# IO_IIC.net
KiCad netlist of a schematic drawn in Altium Designer
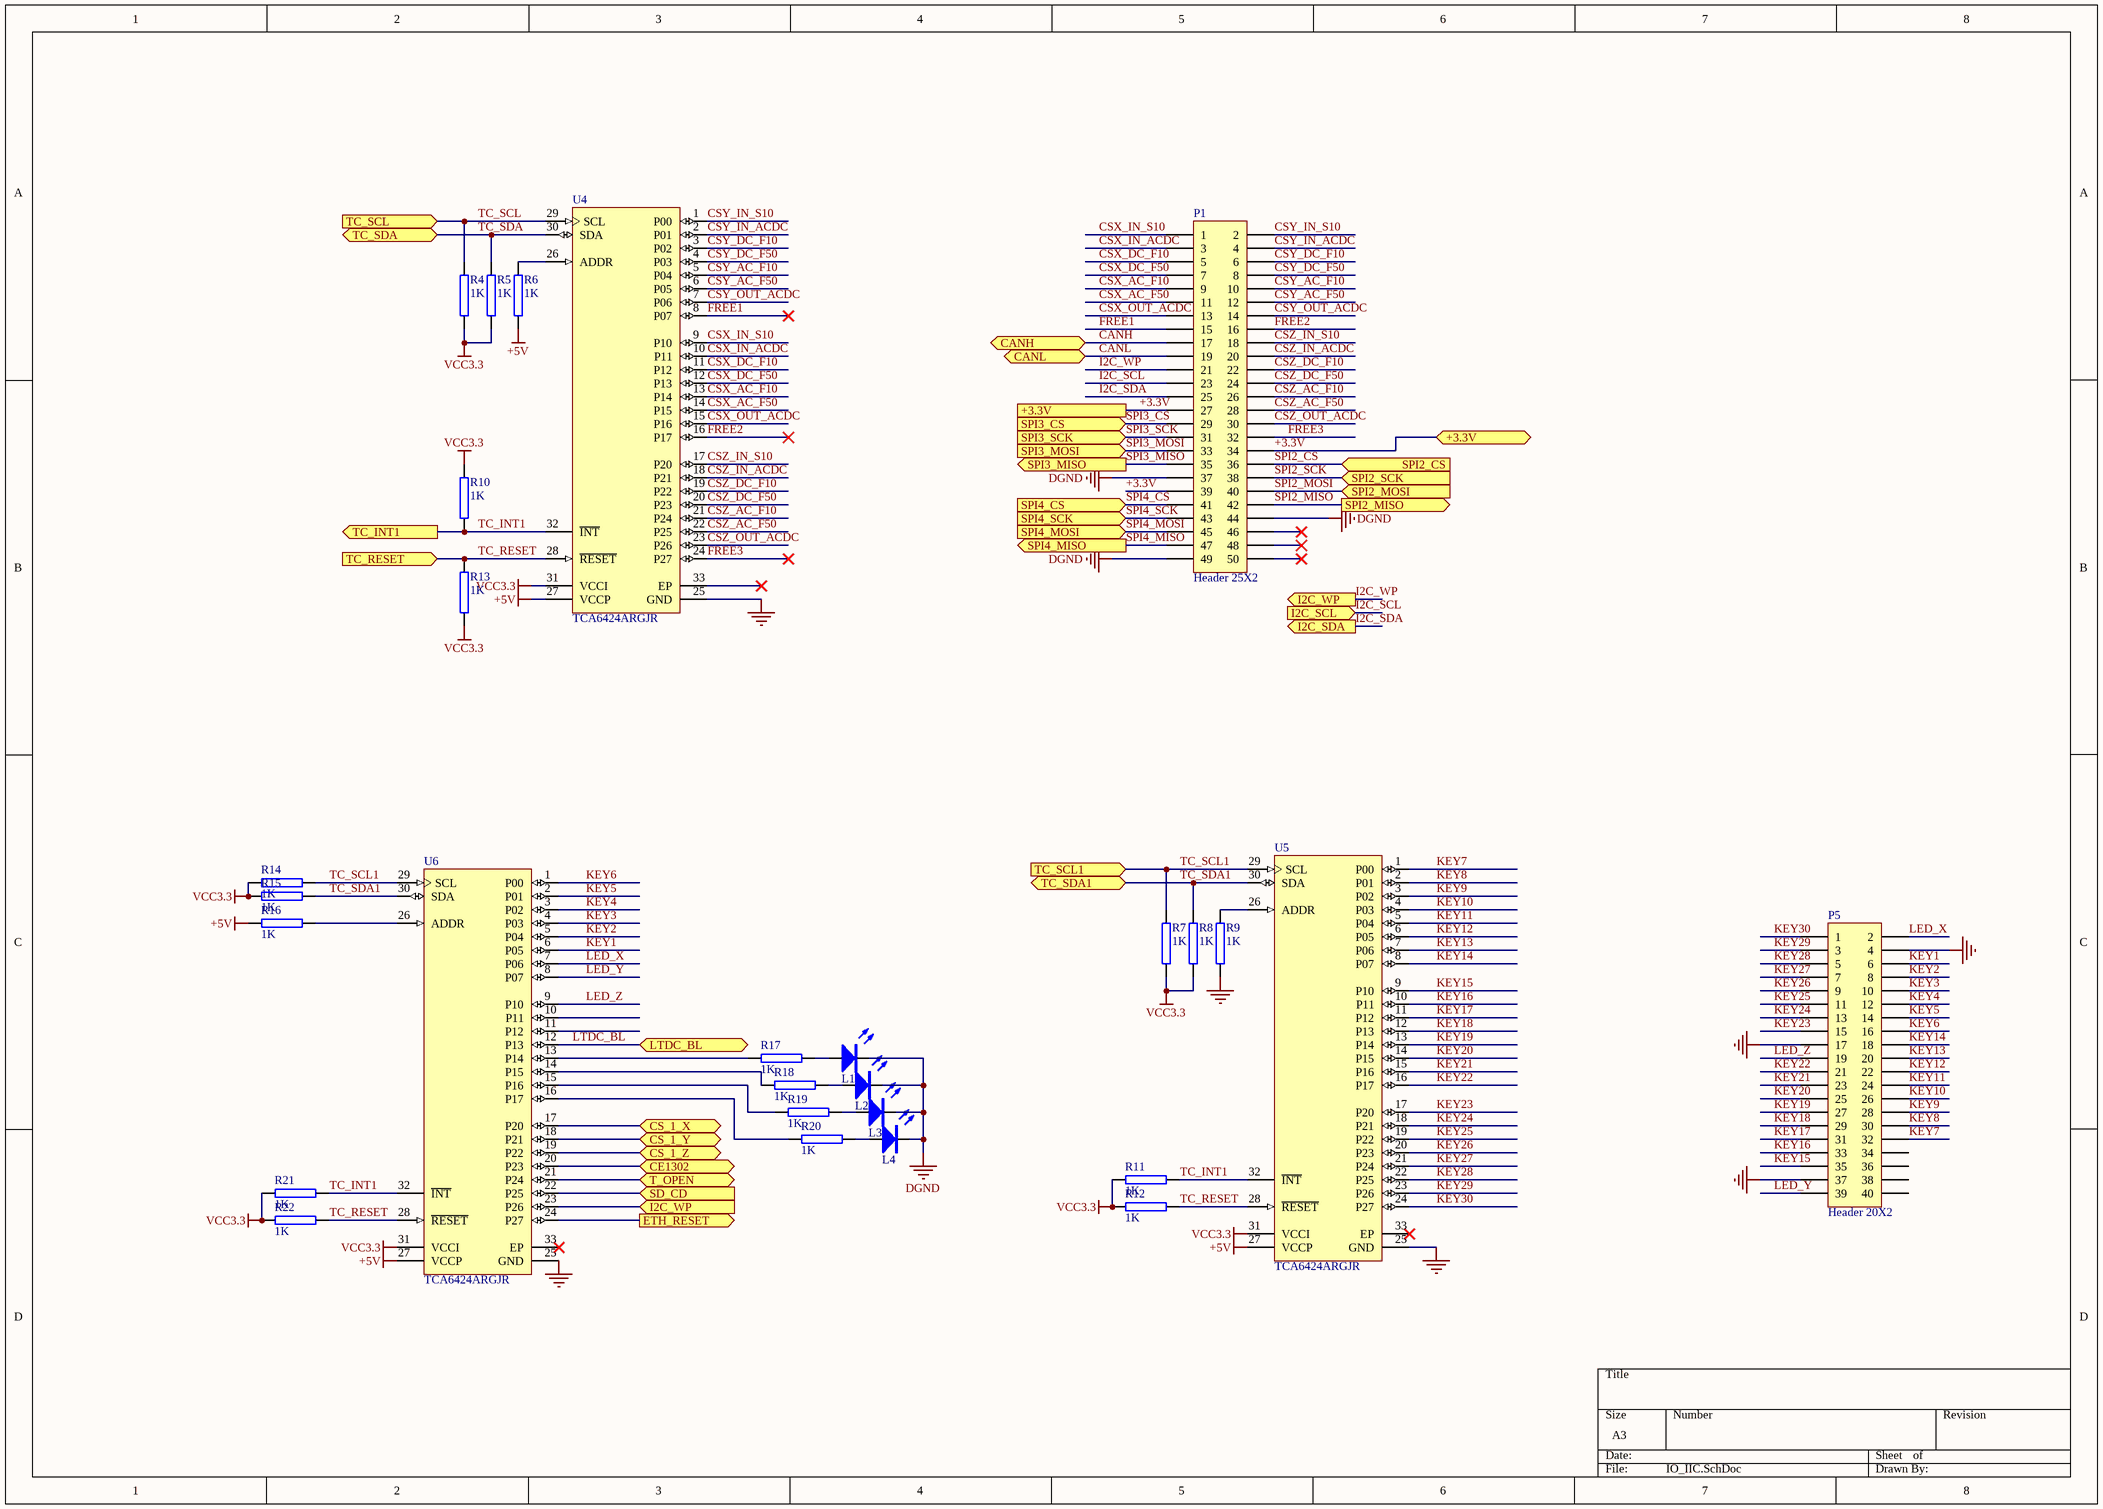
[diagram p0: IO_IIC.SchDoc]

(export (version "E")
  (design (tool "Eeschema 10.0.6"))
  (components
    (comp (ref "L1") (value "LED") (footprint "0805LED") (libsource (lib "二极管") (part "LED")))
    (comp (ref "L2") (value "LED") (footprint "0805LED") (libsource (lib "二极管") (part "LED")))
    (comp (ref "L3") (value "LED") (footprint "0805LED") (libsource (lib "二极管") (part "LED")))
    (comp (ref "L4") (value "LED") (footprint "0805LED") (libsource (lib "二极管") (part "LED")))
    (comp (ref "P1")
      (value "Header 25X2")
      (footprint "HDR2X25")
      (description "Header, 25-Pin, Dual row")
      (fields (field (name "PUBLISHER") "Altium Limited"))
      (libsource (lib "Miscellaneous Connectors") (part "Header 25X2"))
    )
    (comp (ref "P5")
      (value "Header 20X2")
      (footprint "HDR2X20")
      (description "Header, 20-Pin, Dual row")
      (fields (field (name "PUBLISHER") "Altium Limited"))
      (libsource (lib "Miscellaneous Connectors") (part "Header 20X2"))
    )
    (comp (ref "R4") (value "1K") (footprint "0603") (libsource (lib "电阻") (part "RES")))
    (comp (ref "R5") (value "1K") (footprint "0603") (libsource (lib "电阻") (part "RES")))
    (comp (ref "R6") (value "1K") (footprint "0603") (libsource (lib "电阻") (part "RES")))
    (comp (ref "R7") (value "1K") (footprint "0603") (libsource (lib "电阻") (part "RES")))
    (comp (ref "R8") (value "1K") (footprint "0603") (libsource (lib "电阻") (part "RES")))
    (comp (ref "R9") (value "1K") (footprint "0603") (libsource (lib "电阻") (part "RES")))
    (comp (ref "R10") (value "1K") (footprint "0603") (libsource (lib "电阻") (part "RES")))
    (comp (ref "R11") (value "1K") (footprint "0603") (libsource (lib "电阻") (part "RES")))
    (comp (ref "R12") (value "1K") (footprint "0603") (libsource (lib "电阻") (part "RES")))
    (comp (ref "R13") (value "1K") (footprint "0603") (libsource (lib "电阻") (part "RES")))
    (comp (ref "R14") (value "1K") (footprint "0603") (libsource (lib "电阻") (part "RES")))
    (comp (ref "R15") (value "1K") (footprint "0603") (libsource (lib "电阻") (part "RES")))
    (comp (ref "R16") (value "1K") (footprint "0603") (libsource (lib "电阻") (part "RES")))
    (comp (ref "R17") (value "1K") (footprint "0603") (libsource (lib "电阻") (part "RES")))
    (comp (ref "R18") (value "1K") (footprint "0603") (libsource (lib "电阻") (part "RES")))
    (comp (ref "R19") (value "1K") (footprint "0603") (libsource (lib "电阻") (part "RES")))
    (comp (ref "R20") (value "1K") (footprint "0603") (libsource (lib "电阻") (part "RES")))
    (comp (ref "R21") (value "1K") (footprint "0603") (libsource (lib "电阻") (part "RES")))
    (comp (ref "R22") (value "1K") (footprint "0603") (libsource (lib "电阻") (part "RES")))
    (comp (ref "U4")
      (value "TCA6424ARGJR")
      (footprint "TCA6424A-QFN32")
      (fields (field (name "MANUFACTURER") "Texas Instruments"))
      (libsource (lib "Texas Instruments Interface I2C") (part "TCA6424ARGJR"))
    )
    (comp (ref "U5")
      (value "TCA6424ARGJR")
      (footprint "TCA6424A-QFN32")
      (fields (field (name "MANUFACTURER") "Texas Instruments"))
      (libsource (lib "Texas Instruments Interface I2C") (part "TCA6424ARGJR"))
    )
    (comp (ref "U6")
      (value "TCA6424ARGJR")
      (footprint "TCA6424A-QFN32")
      (fields (field (name "MANUFACTURER") "Texas Instruments"))
      (libsource (lib "Texas Instruments Interface I2C") (part "TCA6424ARGJR"))
    )
  )
  (nets
    (net (code "1") (name "+5V") (class "Default")
      (node (ref "R16") (pin "2") (pinfunction "2_2") (pintype "passive"))
      (node (ref "R6") (pin "2") (pinfunction "2_2") (pintype "passive"))
      (node (ref "U4") (pin "27") (pinfunction "VCCP_27") (pintype "power_in"))
      (node (ref "U5") (pin "27") (pinfunction "VCCP_27") (pintype "power_in"))
      (node (ref "U6") (pin "27") (pinfunction "VCCP_27") (pintype "power_in"))
    )
    (net (code "2") (name "/+3.3V") (class "Default")
      (node (ref "P1") (pin "27") (pinfunction "27_27") (pintype "passive"))
      (node (ref "P1") (pin "34") (pinfunction "34_34") (pintype "passive"))
      (node (ref "P1") (pin "39") (pinfunction "39_39") (pintype "passive"))
    )
    (net (code "3") (name "/CANH") (class "Default")
      (node (ref "P1") (pin "17") (pinfunction "17_17") (pintype "passive"))
    )
    (net (code "4") (name "/CANL") (class "Default")
      (node (ref "P1") (pin "19") (pinfunction "19_19") (pintype "passive"))
    )
    (net (code "5") (name "/CE1302") (class "Default")
      (node (ref "U6") (pin "20") (pinfunction "P23_20") (pintype "bidirectional"))
    )
    (net (code "6") (name "/CSX_AC_F10") (class "Default")
      (node (ref "P1") (pin "9") (pinfunction "9_9") (pintype "passive"))
      (node (ref "U4") (pin "13") (pinfunction "P14_13") (pintype "bidirectional"))
    )
    (net (code "7") (name "/CSX_AC_F50") (class "Default")
      (node (ref "P1") (pin "11") (pinfunction "11_11") (pintype "passive"))
      (node (ref "U4") (pin "14") (pinfunction "P15_14") (pintype "bidirectional"))
    )
    (net (code "8") (name "/CSX_DC_F10") (class "Default")
      (node (ref "P1") (pin "5") (pinfunction "5_5") (pintype "passive"))
      (node (ref "U4") (pin "11") (pinfunction "P12_11") (pintype "bidirectional"))
    )
    (net (code "9") (name "/CSX_DC_F50") (class "Default")
      (node (ref "P1") (pin "7") (pinfunction "7_7") (pintype "passive"))
      (node (ref "U4") (pin "12") (pinfunction "P13_12") (pintype "bidirectional"))
    )
    (net (code "10") (name "/CSX_IN_ACDC") (class "Default")
      (node (ref "P1") (pin "3") (pinfunction "3_3") (pintype "passive"))
      (node (ref "U4") (pin "10") (pinfunction "P11_10") (pintype "bidirectional"))
    )
    (net (code "11") (name "/CSX_IN_S10") (class "Default")
      (node (ref "P1") (pin "1") (pinfunction "1_1") (pintype "passive"))
      (node (ref "U4") (pin "9") (pinfunction "P10_9") (pintype "bidirectional"))
    )
    (net (code "12") (name "/CSX_OUT_ACDC") (class "Default")
      (node (ref "P1") (pin "13") (pinfunction "13_13") (pintype "passive"))
      (node (ref "U4") (pin "15") (pinfunction "P16_15") (pintype "bidirectional"))
    )
    (net (code "13") (name "/CSY_AC_F10") (class "Default")
      (node (ref "P1") (pin "10") (pinfunction "10_10") (pintype "passive"))
      (node (ref "U4") (pin "5") (pinfunction "P04_5") (pintype "bidirectional"))
    )
    (net (code "14") (name "/CSY_AC_F50") (class "Default")
      (node (ref "P1") (pin "12") (pinfunction "12_12") (pintype "passive"))
      (node (ref "U4") (pin "6") (pinfunction "P05_6") (pintype "bidirectional"))
    )
    (net (code "15") (name "/CSY_DC_F10") (class "Default")
      (node (ref "P1") (pin "6") (pinfunction "6_6") (pintype "passive"))
      (node (ref "U4") (pin "3") (pinfunction "P02_3") (pintype "bidirectional"))
    )
    (net (code "16") (name "/CSY_DC_F50") (class "Default")
      (node (ref "P1") (pin "8") (pinfunction "8_8") (pintype "passive"))
      (node (ref "U4") (pin "4") (pinfunction "P03_4") (pintype "bidirectional"))
    )
    (net (code "17") (name "/CSY_IN_ACDC") (class "Default")
      (node (ref "P1") (pin "4") (pinfunction "4_4") (pintype "passive"))
      (node (ref "U4") (pin "2") (pinfunction "P01_2") (pintype "bidirectional"))
    )
    (net (code "18") (name "/CSY_IN_S10") (class "Default")
      (node (ref "P1") (pin "2") (pinfunction "2_2") (pintype "passive"))
      (node (ref "U4") (pin "1") (pinfunction "P00_1") (pintype "bidirectional"))
    )
    (net (code "19") (name "/CSY_OUT_ACDC") (class "Default")
      (node (ref "P1") (pin "14") (pinfunction "14_14") (pintype "passive"))
      (node (ref "U4") (pin "7") (pinfunction "P06_7") (pintype "bidirectional"))
    )
    (net (code "20") (name "/CSZ_AC_F10") (class "Default")
      (node (ref "P1") (pin "26") (pinfunction "26_26") (pintype "passive"))
      (node (ref "U4") (pin "21") (pinfunction "P24_21") (pintype "bidirectional"))
    )
    (net (code "21") (name "/CSZ_AC_F50") (class "Default")
      (node (ref "P1") (pin "28") (pinfunction "28_28") (pintype "passive"))
      (node (ref "U4") (pin "22") (pinfunction "P25_22") (pintype "bidirectional"))
    )
    (net (code "22") (name "/CSZ_DC_F10") (class "Default")
      (node (ref "P1") (pin "22") (pinfunction "22_22") (pintype "passive"))
      (node (ref "U4") (pin "19") (pinfunction "P22_19") (pintype "bidirectional"))
    )
    (net (code "23") (name "/CSZ_DC_F50") (class "Default")
      (node (ref "P1") (pin "24") (pinfunction "24_24") (pintype "passive"))
      (node (ref "U4") (pin "20") (pinfunction "P23_20") (pintype "bidirectional"))
    )
    (net (code "24") (name "/CSZ_IN_ACDC") (class "Default")
      (node (ref "P1") (pin "20") (pinfunction "20_20") (pintype "passive"))
      (node (ref "U4") (pin "18") (pinfunction "P21_18") (pintype "bidirectional"))
    )
    (net (code "25") (name "/CSZ_IN_S10") (class "Default")
      (node (ref "P1") (pin "18") (pinfunction "18_18") (pintype "passive"))
      (node (ref "U4") (pin "17") (pinfunction "P20_17") (pintype "bidirectional"))
    )
    (net (code "26") (name "/CSZ_OUT_ACDC") (class "Default")
      (node (ref "P1") (pin "30") (pinfunction "30_30") (pintype "passive"))
      (node (ref "U4") (pin "23") (pinfunction "P26_23") (pintype "bidirectional"))
    )
    (net (code "27") (name "/CS_1_X") (class "Default")
      (node (ref "U6") (pin "17") (pinfunction "P20_17") (pintype "bidirectional"))
    )
    (net (code "28") (name "/CS_1_Y") (class "Default")
      (node (ref "U6") (pin "18") (pinfunction "P21_18") (pintype "bidirectional"))
    )
    (net (code "29") (name "/CS_1_Z") (class "Default")
      (node (ref "U6") (pin "19") (pinfunction "P22_19") (pintype "bidirectional"))
    )
    (net (code "30") (name "/ETH_RESET") (class "Default")
      (node (ref "U6") (pin "24") (pinfunction "P27_24") (pintype "bidirectional"))
    )
    (net (code "31") (name "/FREE1") (class "Default")
      (node (ref "P1") (pin "15") (pinfunction "15_15") (pintype "passive"))
      (node (ref "U4") (pin "8") (pinfunction "P07_8") (pintype "bidirectional"))
    )
    (net (code "32") (name "/FREE2") (class "Default")
      (node (ref "P1") (pin "16") (pinfunction "16_16") (pintype "passive"))
      (node (ref "U4") (pin "16") (pinfunction "P17_16") (pintype "bidirectional"))
    )
    (net (code "33") (name "/FREE3") (class "Default")
      (node (ref "P1") (pin "32") (pinfunction "32_32") (pintype "passive"))
      (node (ref "U4") (pin "24") (pinfunction "P27_24") (pintype "bidirectional"))
    )
    (net (code "34") (name "/I2C_SCL") (class "Default")
      (node (ref "P1") (pin "23") (pinfunction "23_23") (pintype "passive"))
    )
    (net (code "35") (name "/I2C_SDA") (class "Default")
      (node (ref "P1") (pin "25") (pinfunction "25_25") (pintype "passive"))
    )
    (net (code "36") (name "/I2C_WP") (class "Default")
      (node (ref "P1") (pin "21") (pinfunction "21_21") (pintype "passive"))
      (node (ref "U6") (pin "23") (pinfunction "P26_23") (pintype "bidirectional"))
    )
    (net (code "37") (name "/KEY1") (class "Default")
      (node (ref "P5") (pin "6") (pinfunction "6_6") (pintype "passive"))
      (node (ref "U6") (pin "6") (pinfunction "P05_6") (pintype "bidirectional"))
    )
    (net (code "38") (name "/KEY2") (class "Default")
      (node (ref "P5") (pin "8") (pinfunction "8_8") (pintype "passive"))
      (node (ref "U6") (pin "5") (pinfunction "P04_5") (pintype "bidirectional"))
    )
    (net (code "39") (name "/KEY3") (class "Default")
      (node (ref "P5") (pin "10") (pinfunction "10_10") (pintype "passive"))
      (node (ref "U6") (pin "4") (pinfunction "P03_4") (pintype "bidirectional"))
    )
    (net (code "40") (name "/KEY4") (class "Default")
      (node (ref "P5") (pin "12") (pinfunction "12_12") (pintype "passive"))
      (node (ref "U6") (pin "3") (pinfunction "P02_3") (pintype "bidirectional"))
    )
    (net (code "41") (name "/KEY5") (class "Default")
      (node (ref "P5") (pin "14") (pinfunction "14_14") (pintype "passive"))
      (node (ref "U6") (pin "2") (pinfunction "P01_2") (pintype "bidirectional"))
    )
    (net (code "42") (name "/KEY6") (class "Default")
      (node (ref "P5") (pin "16") (pinfunction "16_16") (pintype "passive"))
      (node (ref "U6") (pin "1") (pinfunction "P00_1") (pintype "bidirectional"))
    )
    (net (code "43") (name "/KEY7") (class "Default")
      (node (ref "P5") (pin "32") (pinfunction "32_32") (pintype "passive"))
      (node (ref "U5") (pin "1") (pinfunction "P00_1") (pintype "bidirectional"))
    )
    (net (code "44") (name "/KEY8") (class "Default")
      (node (ref "P5") (pin "30") (pinfunction "30_30") (pintype "passive"))
      (node (ref "U5") (pin "2") (pinfunction "P01_2") (pintype "bidirectional"))
    )
    (net (code "45") (name "/KEY9") (class "Default")
      (node (ref "P5") (pin "28") (pinfunction "28_28") (pintype "passive"))
      (node (ref "U5") (pin "3") (pinfunction "P02_3") (pintype "bidirectional"))
    )
    (net (code "46") (name "/KEY10") (class "Default")
      (node (ref "P5") (pin "26") (pinfunction "26_26") (pintype "passive"))
      (node (ref "U5") (pin "4") (pinfunction "P03_4") (pintype "bidirectional"))
    )
    (net (code "47") (name "/KEY11") (class "Default")
      (node (ref "P5") (pin "24") (pinfunction "24_24") (pintype "passive"))
      (node (ref "U5") (pin "5") (pinfunction "P04_5") (pintype "bidirectional"))
    )
    (net (code "48") (name "/KEY12") (class "Default")
      (node (ref "P5") (pin "22") (pinfunction "22_22") (pintype "passive"))
      (node (ref "U5") (pin "6") (pinfunction "P05_6") (pintype "bidirectional"))
    )
    (net (code "49") (name "/KEY13") (class "Default")
      (node (ref "P5") (pin "20") (pinfunction "20_20") (pintype "passive"))
      (node (ref "U5") (pin "7") (pinfunction "P06_7") (pintype "bidirectional"))
    )
    (net (code "50") (name "/KEY14") (class "Default")
      (node (ref "P5") (pin "18") (pinfunction "18_18") (pintype "passive"))
      (node (ref "U5") (pin "8") (pinfunction "P07_8") (pintype "bidirectional"))
    )
    (net (code "51") (name "/KEY15") (class "Default")
      (node (ref "P5") (pin "35") (pinfunction "35_35") (pintype "passive"))
      (node (ref "U5") (pin "9") (pinfunction "P10_9") (pintype "bidirectional"))
    )
    (net (code "52") (name "/KEY16") (class "Default")
      (node (ref "P5") (pin "33") (pinfunction "33_33") (pintype "passive"))
      (node (ref "U5") (pin "10") (pinfunction "P11_10") (pintype "bidirectional"))
    )
    (net (code "53") (name "/KEY17") (class "Default")
      (node (ref "P5") (pin "31") (pinfunction "31_31") (pintype "passive"))
      (node (ref "U5") (pin "11") (pinfunction "P12_11") (pintype "bidirectional"))
    )
    (net (code "54") (name "/KEY18") (class "Default")
      (node (ref "P5") (pin "29") (pinfunction "29_29") (pintype "passive"))
      (node (ref "U5") (pin "12") (pinfunction "P13_12") (pintype "bidirectional"))
    )
    (net (code "55") (name "/KEY19") (class "Default")
      (node (ref "P5") (pin "27") (pinfunction "27_27") (pintype "passive"))
      (node (ref "U5") (pin "13") (pinfunction "P14_13") (pintype "bidirectional"))
    )
    (net (code "56") (name "/KEY20") (class "Default")
      (node (ref "P5") (pin "25") (pinfunction "25_25") (pintype "passive"))
      (node (ref "U5") (pin "14") (pinfunction "P15_14") (pintype "bidirectional"))
    )
    (net (code "57") (name "/KEY21") (class "Default")
      (node (ref "P5") (pin "23") (pinfunction "23_23") (pintype "passive"))
      (node (ref "U5") (pin "15") (pinfunction "P16_15") (pintype "bidirectional"))
    )
    (net (code "58") (name "/KEY22") (class "Default")
      (node (ref "P5") (pin "21") (pinfunction "21_21") (pintype "passive"))
      (node (ref "U5") (pin "16") (pinfunction "P17_16") (pintype "bidirectional"))
    )
    (net (code "59") (name "/KEY23") (class "Default")
      (node (ref "P5") (pin "15") (pinfunction "15_15") (pintype "passive"))
      (node (ref "U5") (pin "17") (pinfunction "P20_17") (pintype "bidirectional"))
    )
    (net (code "60") (name "/KEY24") (class "Default")
      (node (ref "P5") (pin "13") (pinfunction "13_13") (pintype "passive"))
      (node (ref "U5") (pin "18") (pinfunction "P21_18") (pintype "bidirectional"))
    )
    (net (code "61") (name "/KEY25") (class "Default")
      (node (ref "P5") (pin "11") (pinfunction "11_11") (pintype "passive"))
      (node (ref "U5") (pin "19") (pinfunction "P22_19") (pintype "bidirectional"))
    )
    (net (code "62") (name "/KEY26") (class "Default")
      (node (ref "P5") (pin "9") (pinfunction "9_9") (pintype "passive"))
      (node (ref "U5") (pin "20") (pinfunction "P23_20") (pintype "bidirectional"))
    )
    (net (code "63") (name "/KEY27") (class "Default")
      (node (ref "P5") (pin "7") (pinfunction "7_7") (pintype "passive"))
      (node (ref "U5") (pin "21") (pinfunction "P24_21") (pintype "bidirectional"))
    )
    (net (code "64") (name "/KEY28") (class "Default")
      (node (ref "P5") (pin "5") (pinfunction "5_5") (pintype "passive"))
      (node (ref "U5") (pin "22") (pinfunction "P25_22") (pintype "bidirectional"))
    )
    (net (code "65") (name "/KEY29") (class "Default")
      (node (ref "P5") (pin "3") (pinfunction "3_3") (pintype "passive"))
      (node (ref "U5") (pin "23") (pinfunction "P26_23") (pintype "bidirectional"))
    )
    (net (code "66") (name "/KEY30") (class "Default")
      (node (ref "P5") (pin "1") (pinfunction "1_1") (pintype "passive"))
      (node (ref "U5") (pin "24") (pinfunction "P27_24") (pintype "bidirectional"))
    )
    (net (code "67") (name "/LED_X") (class "Default")
      (node (ref "P5") (pin "2") (pinfunction "2_2") (pintype "passive"))
      (node (ref "U6") (pin "7") (pinfunction "P06_7") (pintype "bidirectional"))
    )
    (net (code "68") (name "/LED_Y") (class "Default")
      (node (ref "P5") (pin "39") (pinfunction "39_39") (pintype "passive"))
      (node (ref "U6") (pin "8") (pinfunction "P07_8") (pintype "bidirectional"))
    )
    (net (code "69") (name "/LED_Z") (class "Default")
      (node (ref "P5") (pin "19") (pinfunction "19_19") (pintype "passive"))
      (node (ref "U6") (pin "9") (pinfunction "P10_9") (pintype "bidirectional"))
    )
    (net (code "70") (name "/LTDC_BL") (class "Default")
      (node (ref "U6") (pin "12") (pinfunction "P13_12") (pintype "bidirectional"))
    )
    (net (code "71") (name "/SD_CD") (class "Default")
      (node (ref "U6") (pin "22") (pinfunction "P25_22") (pintype "bidirectional"))
    )
    (net (code "72") (name "/SPI2_CS") (class "Default")
      (node (ref "P1") (pin "36") (pinfunction "36_36") (pintype "passive"))
    )
    (net (code "73") (name "/SPI2_MISO") (class "Default")
      (node (ref "P1") (pin "42") (pinfunction "42_42") (pintype "passive"))
    )
    (net (code "74") (name "/SPI2_MOSI") (class "Default")
      (node (ref "P1") (pin "40") (pinfunction "40_40") (pintype "passive"))
    )
    (net (code "75") (name "/SPI2_SCK") (class "Default")
      (node (ref "P1") (pin "38") (pinfunction "38_38") (pintype "passive"))
    )
    (net (code "76") (name "/SPI3_CS") (class "Default")
      (node (ref "P1") (pin "29") (pinfunction "29_29") (pintype "passive"))
    )
    (net (code "77") (name "/SPI3_MISO") (class "Default")
      (node (ref "P1") (pin "35") (pinfunction "35_35") (pintype "passive"))
    )
    (net (code "78") (name "/SPI3_MOSI") (class "Default")
      (node (ref "P1") (pin "33") (pinfunction "33_33") (pintype "passive"))
    )
    (net (code "79") (name "/SPI3_SCK") (class "Default")
      (node (ref "P1") (pin "31") (pinfunction "31_31") (pintype "passive"))
    )
    (net (code "80") (name "/SPI4_CS") (class "Default")
      (node (ref "P1") (pin "41") (pinfunction "41_41") (pintype "passive"))
    )
    (net (code "81") (name "/SPI4_MISO") (class "Default")
      (node (ref "P1") (pin "47") (pinfunction "47_47") (pintype "passive"))
    )
    (net (code "82") (name "/SPI4_MOSI") (class "Default")
      (node (ref "P1") (pin "45") (pinfunction "45_45") (pintype "passive"))
    )
    (net (code "83") (name "/SPI4_SCK") (class "Default")
      (node (ref "P1") (pin "43") (pinfunction "43_43") (pintype "passive"))
    )
    (net (code "84") (name "/TC_INT1") (class "Default")
      (node (ref "R10") (pin "1") (pinfunction "1_1") (pintype "passive"))
      (node (ref "R11") (pin "1") (pinfunction "1_1") (pintype "passive"))
      (node (ref "R21") (pin "1") (pinfunction "1_1") (pintype "passive"))
      (node (ref "U4") (pin "32") (pinfunction "~{INT}_32") (pintype "open_collector"))
      (node (ref "U5") (pin "32") (pinfunction "~{INT}_32") (pintype "open_collector"))
      (node (ref "U6") (pin "32") (pinfunction "~{INT}_32") (pintype "open_collector"))
    )
    (net (code "85") (name "/TC_RESET") (class "Default")
      (node (ref "R12") (pin "1") (pinfunction "1_1") (pintype "passive"))
      (node (ref "R13") (pin "2") (pinfunction "2_2") (pintype "passive"))
      (node (ref "R22") (pin "1") (pinfunction "1_1") (pintype "passive"))
      (node (ref "U4") (pin "28") (pinfunction "~{RESET}_28") (pintype "input"))
      (node (ref "U5") (pin "28") (pinfunction "~{RESET}_28") (pintype "input"))
      (node (ref "U6") (pin "28") (pinfunction "~{RESET}_28") (pintype "input"))
    )
    (net (code "86") (name "/TC_SCL") (class "Default")
      (node (ref "R4") (pin "1") (pinfunction "1_1") (pintype "passive"))
      (node (ref "U4") (pin "29") (pinfunction "SCL_29") (pintype "input"))
    )
    (net (code "87") (name "/TC_SCL1") (class "Default")
      (node (ref "R14") (pin "1") (pinfunction "1_1") (pintype "passive"))
      (node (ref "R7") (pin "1") (pinfunction "1_1") (pintype "passive"))
      (node (ref "U5") (pin "29") (pinfunction "SCL_29") (pintype "input"))
      (node (ref "U6") (pin "29") (pinfunction "SCL_29") (pintype "input"))
    )
    (net (code "88") (name "/TC_SDA") (class "Default")
      (node (ref "R5") (pin "1") (pinfunction "1_1") (pintype "passive"))
      (node (ref "U4") (pin "30") (pinfunction "SDA_30") (pintype "bidirectional"))
    )
    (net (code "89") (name "/TC_SDA1") (class "Default")
      (node (ref "R15") (pin "1") (pinfunction "1_1") (pintype "passive"))
      (node (ref "R8") (pin "1") (pinfunction "1_1") (pintype "passive"))
      (node (ref "U5") (pin "30") (pinfunction "SDA_30") (pintype "bidirectional"))
      (node (ref "U6") (pin "30") (pinfunction "SDA_30") (pintype "bidirectional"))
    )
    (net (code "90") (name "/T_OPEN") (class "Default")
      (node (ref "U6") (pin "21") (pinfunction "P24_21") (pintype "bidirectional"))
    )
    (net (code "91") (name "DGND") (class "Default")
      (node (ref "L1") (pin "2") (pinfunction "K_2") (pintype "passive"))
      (node (ref "L2") (pin "2") (pinfunction "K_2") (pintype "passive"))
      (node (ref "L3") (pin "2") (pinfunction "K_2") (pintype "passive"))
      (node (ref "L4") (pin "2") (pinfunction "K_2") (pintype "passive"))
      (node (ref "P1") (pin "37") (pinfunction "37_37") (pintype "passive"))
      (node (ref "P1") (pin "44") (pinfunction "44_44") (pintype "passive"))
      (node (ref "P1") (pin "49") (pinfunction "49_49") (pintype "passive"))
      (node (ref "P5") (pin "17") (pinfunction "17_17") (pintype "passive"))
      (node (ref "P5") (pin "37") (pinfunction "37_37") (pintype "passive"))
      (node (ref "P5") (pin "4") (pinfunction "4_4") (pintype "passive"))
      (node (ref "R9") (pin "2") (pinfunction "2_2") (pintype "passive"))
      (node (ref "U4") (pin "25") (pinfunction "GND_25") (pintype "power_in"))
      (node (ref "U5") (pin "25") (pinfunction "GND_25") (pintype "power_in"))
      (node (ref "U6") (pin "25") (pinfunction "GND_25") (pintype "power_in"))
    )
    (net (code "92") (name "Net-(L1-A)") (class "Default")
      (node (ref "L1") (pin "1") (pinfunction "A_1") (pintype "passive"))
      (node (ref "R17") (pin "1") (pinfunction "1_1") (pintype "passive"))
    )
    (net (code "93") (name "Net-(L2-A)") (class "Default")
      (node (ref "L2") (pin "1") (pinfunction "A_1") (pintype "passive"))
      (node (ref "R18") (pin "1") (pinfunction "1_1") (pintype "passive"))
    )
    (net (code "94") (name "Net-(L3-A)") (class "Default")
      (node (ref "L3") (pin "1") (pinfunction "A_1") (pintype "passive"))
      (node (ref "R19") (pin "1") (pinfunction "1_1") (pintype "passive"))
    )
    (net (code "95") (name "Net-(L4-A)") (class "Default")
      (node (ref "L4") (pin "1") (pinfunction "A_1") (pintype "passive"))
      (node (ref "R20") (pin "1") (pinfunction "1_1") (pintype "passive"))
    )
    (net (code "96") (name "Net-(U4-ADDR)") (class "Default")
      (node (ref "R6") (pin "1") (pinfunction "1_1") (pintype "passive"))
      (node (ref "U4") (pin "26") (pinfunction "ADDR_26") (pintype "input"))
    )
    (net (code "97") (name "Net-(U5-ADDR)") (class "Default")
      (node (ref "R9") (pin "1") (pinfunction "1_1") (pintype "passive"))
      (node (ref "U5") (pin "26") (pinfunction "ADDR_26") (pintype "input"))
    )
    (net (code "98") (name "Net-(U6-ADDR)") (class "Default")
      (node (ref "R16") (pin "1") (pinfunction "1_1") (pintype "passive"))
      (node (ref "U6") (pin "26") (pinfunction "ADDR_26") (pintype "input"))
    )
    (net (code "99") (name "Net-(U6-P14)") (class "Default")
      (node (ref "R17") (pin "2") (pinfunction "2_2") (pintype "passive"))
      (node (ref "U6") (pin "13") (pinfunction "P14_13") (pintype "bidirectional"))
    )
    (net (code "100") (name "Net-(U6-P15)") (class "Default")
      (node (ref "R18") (pin "2") (pinfunction "2_2") (pintype "passive"))
      (node (ref "U6") (pin "14") (pinfunction "P15_14") (pintype "bidirectional"))
    )
    (net (code "101") (name "Net-(U6-P16)") (class "Default")
      (node (ref "R19") (pin "2") (pinfunction "2_2") (pintype "passive"))
      (node (ref "U6") (pin "15") (pinfunction "P16_15") (pintype "bidirectional"))
    )
    (net (code "102") (name "Net-(U6-P17)") (class "Default")
      (node (ref "R20") (pin "2") (pinfunction "2_2") (pintype "passive"))
      (node (ref "U6") (pin "16") (pinfunction "P17_16") (pintype "bidirectional"))
    )
    (net (code "103") (name "VCC3.3") (class "Default")
      (node (ref "R10") (pin "2") (pinfunction "2_2") (pintype "passive"))
      (node (ref "R11") (pin "2") (pinfunction "2_2") (pintype "passive"))
      (node (ref "R12") (pin "2") (pinfunction "2_2") (pintype "passive"))
      (node (ref "R13") (pin "1") (pinfunction "1_1") (pintype "passive"))
      (node (ref "R14") (pin "2") (pinfunction "2_2") (pintype "passive"))
      (node (ref "R15") (pin "2") (pinfunction "2_2") (pintype "passive"))
      (node (ref "R21") (pin "2") (pinfunction "2_2") (pintype "passive"))
      (node (ref "R22") (pin "2") (pinfunction "2_2") (pintype "passive"))
      (node (ref "R4") (pin "2") (pinfunction "2_2") (pintype "passive"))
      (node (ref "R5") (pin "2") (pinfunction "2_2") (pintype "passive"))
      (node (ref "R7") (pin "2") (pinfunction "2_2") (pintype "passive"))
      (node (ref "R8") (pin "2") (pinfunction "2_2") (pintype "passive"))
      (node (ref "U4") (pin "31") (pinfunction "VCCI_31") (pintype "power_in"))
      (node (ref "U5") (pin "31") (pinfunction "VCCI_31") (pintype "power_in"))
      (node (ref "U6") (pin "31") (pinfunction "VCCI_31") (pintype "power_in"))
    )
    (net (code "104") (name "unconnected-(P1-Pad46)") (class "Default")
      (node (ref "P1") (pin "46") (pinfunction "46_46") (pintype "passive+no_connect"))
    )
    (net (code "105") (name "unconnected-(P1-Pad48)") (class "Default")
      (node (ref "P1") (pin "48") (pinfunction "48_48") (pintype "passive+no_connect"))
    )
    (net (code "106") (name "unconnected-(P1-Pad50)") (class "Default")
      (node (ref "P1") (pin "50") (pinfunction "50_50") (pintype "passive+no_connect"))
    )
    (net (code "107") (name "unconnected-(P5-Pad34)") (class "Default")
      (node (ref "P5") (pin "34") (pinfunction "34_34") (pintype "passive"))
    )
    (net (code "108") (name "unconnected-(P5-Pad36)") (class "Default")
      (node (ref "P5") (pin "36") (pinfunction "36_36") (pintype "passive"))
    )
    (net (code "109") (name "unconnected-(P5-Pad38)") (class "Default")
      (node (ref "P5") (pin "38") (pinfunction "38_38") (pintype "passive"))
    )
    (net (code "110") (name "unconnected-(P5-Pad40)") (class "Default")
      (node (ref "P5") (pin "40") (pinfunction "40_40") (pintype "passive"))
    )
    (net (code "111") (name "unconnected-(U4-EP-Pad33)") (class "Default")
      (node (ref "U4") (pin "33") (pinfunction "EP_33") (pintype "passive+no_connect"))
    )
    (net (code "112") (name "unconnected-(U5-EP-Pad33)") (class "Default")
      (node (ref "U5") (pin "33") (pinfunction "EP_33") (pintype "passive+no_connect"))
    )
    (net (code "113") (name "unconnected-(U6-EP-Pad33)") (class "Default")
      (node (ref "U6") (pin "33") (pinfunction "EP_33") (pintype "passive+no_connect"))
    )
    (net (code "114") (name "unconnected-(U6-P11-Pad10)") (class "Default")
      (node (ref "U6") (pin "10") (pinfunction "P11_10") (pintype "bidirectional"))
    )
    (net (code "115") (name "unconnected-(U6-P12-Pad11)") (class "Default")
      (node (ref "U6") (pin "11") (pinfunction "P12_11") (pintype "bidirectional"))
    )
  )
)
